# ADC-QCHANNEL_INPUT.net
KiCad netlist of a schematic drawn in Altium Designer
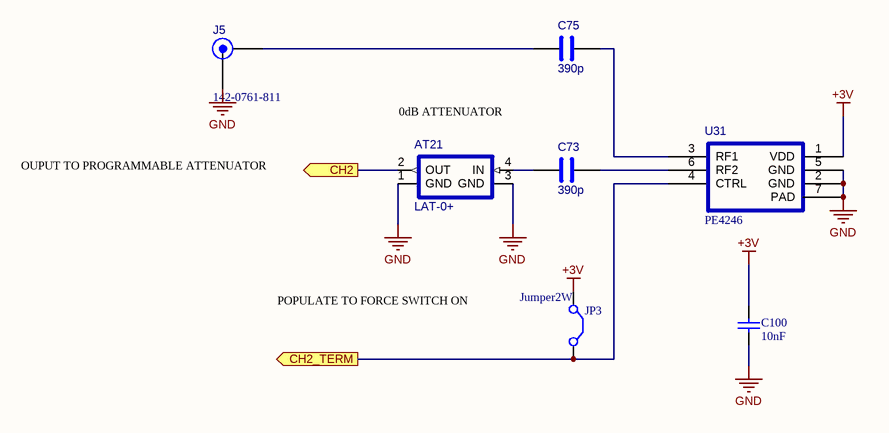
[diagram p0: ADC-QCHANNEL INPUT.SchDoc]

(export (version "E")
  (design (tool "Eeschema 10.0.6"))
  (components
    (comp (ref "AT21")
      (value "~")
      (footprint "MINICIRCUITS_MMM168")
      (description "Fixed Attenuator")
      (fields
        (field (name "MANUFACTURER") "Mini-Circuits")
        (field (name "MANUFACTURER_PN") "LAT-0+")
        (field (name "CREATED_BY") "CT")
        (field (name "CHECKED_BY") "*")
      )
      (libsource (lib "Charles-TEMP") (part "LAT-0+"))
    )
    (comp (ref "C73")
      (value "390p")
      (footprint "CAPC1005X55N")
      (description "CAP SMD 0603")
      (fields (field (name "CREATED_BY") "*") (field (name "CHECKED_BY") "*"))
      (libsource (lib "Abdus-TEMP") (part "CAP-0603"))
    )
    (comp (ref "C75")
      (value "390p")
      (footprint "CAPC1005X55N")
      (description "CAP SMD 0603")
      (fields (field (name "CREATED_BY") "*") (field (name "CHECKED_BY") "*"))
      (libsource (lib "Abdus-TEMP") (part "CAP-0603"))
    )
    (comp (ref "C100")
      (value "10nF")
      (footprint "CAPC1005X55N")
      (description "Capacitor 0402 SMD")
      (fields (field (name "CREATED_BY") "EDA-ASA") (field (name "CHECKED_BY") "*"))
      (libsource (lib "EDA-Passive") (part "cap0402"))
    )
    (comp (ref "J5")
      (value "~")
      (footprint "EDGE_LAUNCH_TH_SMA")
      (description "High Frequency SMA End Lauch Connector")
      (fields
        (field (name "MANUFACTURER") "JOHNSON")
        (field (name "VOLTAGE") "???")
        (field (name "MANUFACTURER_PN") "142-0761-811")
        (field (name "CREATED_BY") "CT")
        (field (name "CHECKED_BY") "*")
      )
      (libsource (lib "Charles-TEMP") (part "142-0761-811"))
    )
    (comp (ref "JP3")
      (value "Jumper2W")
      (footprint "JUMPER")
      (description "Jumper Wire")
      (fields (field (name "PUBLISHER") "Altium Limited"))
      (libsource (lib "EDA-Hardware") (part "Jumper2W"))
    )
    (comp (ref "U31")
      (value "PE4246")
      (footprint "PSON95P300X300X90-7USR")
      (description "Absorptive SPST UltraCMOS RF Switch")
      (fields
        (field (name "MANUFACTURER") "Pergrime Semiconductor")
        (field (name "CREATED_BY") "IN")
        (field (name "CHECKED_BY") "*")
      )
      (libsource (lib "Ishvah-TEMP") (part "PE4246"))
    )
  )
  (nets
    (net (code "1") (name "+3V") (class "Default")
      (node (ref "C100") (pin "1") (pinfunction "1_1") (pintype "passive"))
      (node (ref "JP3") (pin "1") (pinfunction "C1_1") (pintype "passive"))
      (node (ref "U31") (pin "1") (pinfunction "VDD_1") (pintype "passive"))
    )
    (net (code "2") (name "/CH2") (class "Default")
      (node (ref "AT21") (pin "2") (pinfunction "OUT_2") (pintype "output"))
    )
    (net (code "3") (name "/CH2_TERM") (class "Default")
      (node (ref "JP3") (pin "2") (pinfunction "C2_2") (pintype "passive"))
      (node (ref "U31") (pin "4") (pinfunction "CTRL_4") (pintype "passive"))
    )
    (net (code "4") (name "GND") (class "Default")
      (node (ref "AT21") (pin "1") (pinfunction "GND_1") (pintype "power_in"))
      (node (ref "AT21") (pin "3") (pinfunction "GND_3") (pintype "power_in"))
      (node (ref "C100") (pin "2") (pinfunction "2_2") (pintype "passive"))
      (node (ref "J5") (pin "2") (pinfunction "2_2") (pintype "passive"))
      (node (ref "U31") (pin "2") (pinfunction "GND_2") (pintype "passive"))
      (node (ref "U31") (pin "5") (pinfunction "GND_5") (pintype "passive"))
      (node (ref "U31") (pin "7") (pinfunction "PAD_7") (pintype "passive"))
    )
    (net (code "5") (name "Net-(AT21-IN)") (class "Default")
      (node (ref "AT21") (pin "4") (pinfunction "IN_4") (pintype "input"))
      (node (ref "C73") (pin "2") (pinfunction "2_2") (pintype "passive"))
    )
    (net (code "6") (name "Net-(C75-Pad1)") (class "Default")
      (node (ref "C75") (pin "1") (pinfunction "1_1") (pintype "passive"))
      (node (ref "J5") (pin "1") (pinfunction "1_1") (pintype "passive"))
    )
    (net (code "7") (name "Net-(U31-RF1)") (class "Default")
      (node (ref "C75") (pin "2") (pinfunction "2_2") (pintype "passive"))
      (node (ref "U31") (pin "3") (pinfunction "RF1_3") (pintype "passive"))
    )
    (net (code "8") (name "Net-(U31-RF2)") (class "Default")
      (node (ref "C73") (pin "1") (pinfunction "1_1") (pintype "passive"))
      (node (ref "U31") (pin "6") (pinfunction "RF2_6") (pintype "passive"))
    )
  )
)
